# USBMiniBPower.net
KiCad netlist of a schematic drawn in EAGLE
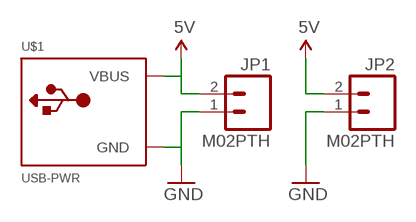
[diagram p0: schematic, sheet 1]

(export (version "E")
  (design (tool "Eeschema 10.0.6"))
  (components
    (comp (ref "JP1")
      (value "M02PTH")
      (footprint "eagle-import:1X02")
      (libsource (lib "eagle-import") (part "M02PTH"))
    )
    (comp (ref "JP2")
      (value "M02PTH")
      (footprint "eagle-import:1X02")
      (libsource (lib "eagle-import") (part "M02PTH"))
    )
    (comp (ref "U$1")
      (value "USB-PWR")
      (footprint "eagle-import:USB-MINIB-THM-MOLEX-PWRONLY")
      (libsource (lib "eagle-import") (part "USB-PWR"))
    )
  )
  (nets
    (net (code "1") (name "5V") (class "Default")
      (node (ref "JP1") (pin "2") (pinfunction "2_2") (pintype "passive"))
      (node (ref "JP2") (pin "2") (pinfunction "2_2") (pintype "passive"))
      (node (ref "U$1") (pin "VBUS") (pinfunction "VBUS_VBUS") (pintype "power_in"))
    )
    (net (code "2") (name "GND") (class "Default")
      (node (ref "JP1") (pin "1") (pinfunction "1_1") (pintype "passive"))
      (node (ref "JP2") (pin "1") (pinfunction "1_1") (pintype "passive"))
      (node (ref "U$1") (pin "GND") (pinfunction "GND_GND") (pintype "power_in"))
    )
  )
)
